# proiect.net
KiCad netlist of a schematic drawn in EAGLE
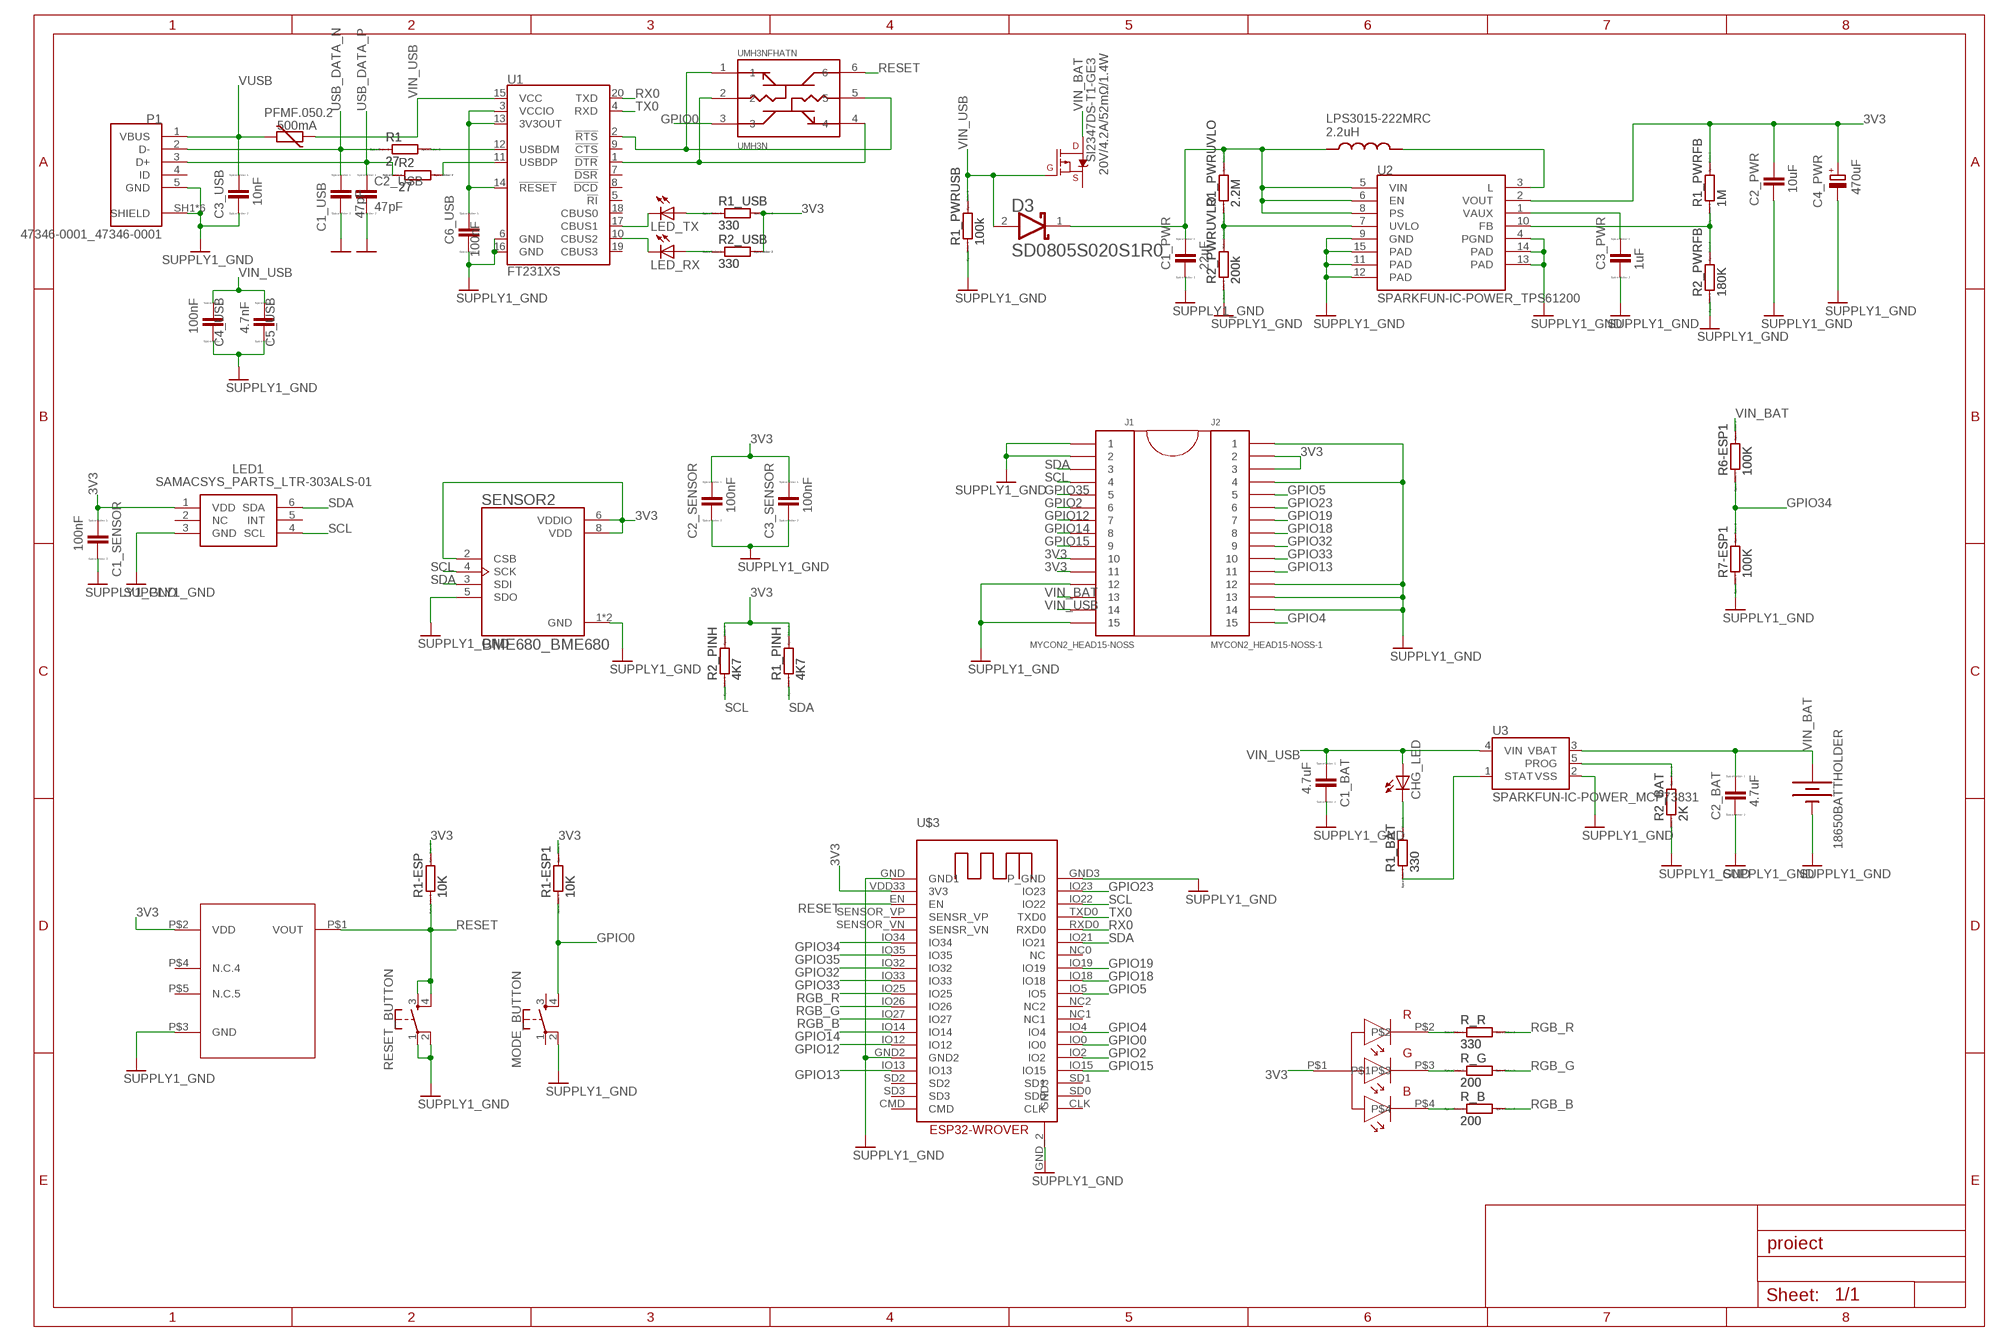
[diagram p0: schematic, sheet 1]

(export (version "E")
  (design (tool "Eeschema 10.0.6"))
  (components
    (comp (ref "18650BATTHOLDER")
      (value "BATTERY-18650")
      (footprint "eagle-import:BATTERY_18650-HOLDER")
      (libsource (lib "eagle-import") (part "BATTERY-18650"))
    )
    (comp (ref "C1_BAT")
      (value "4.7uF")
      (footprint "eagle-import:EAGLE-LTSPICE_C0402")
      (libsource (lib "eagle-import") (part "EAGLE-LTSPICE_CC0402"))
    )
    (comp (ref "C1_PWR")
      (value "22uF")
      (footprint "eagle-import:EAGLE-LTSPICE_C0402")
      (libsource (lib "eagle-import") (part "EAGLE-LTSPICE_CC0402"))
    )
    (comp (ref "C1_SENSOR")
      (value "100nF")
      (footprint "eagle-import:EAGLE-LTSPICE_C0402")
      (libsource (lib "eagle-import") (part "EAGLE-LTSPICE_CC0402"))
    )
    (comp (ref "C1_USB")
      (value "47pF")
      (footprint "eagle-import:EAGLE-LTSPICE_C0402")
      (libsource (lib "eagle-import") (part "EAGLE-LTSPICE_CC0402"))
    )
    (comp (ref "C2_BAT")
      (value "4.7uF")
      (footprint "eagle-import:EAGLE-LTSPICE_C0402")
      (libsource (lib "eagle-import") (part "EAGLE-LTSPICE_CC0402"))
    )
    (comp (ref "C2_PWR")
      (value "10uF")
      (footprint "eagle-import:RCL_C0603")
      (libsource (lib "eagle-import") (part "RCL_C-EUC0603"))
    )
    (comp (ref "C2_SENSOR")
      (value "100nF")
      (footprint "eagle-import:EAGLE-LTSPICE_C0402")
      (libsource (lib "eagle-import") (part "EAGLE-LTSPICE_CC0402"))
    )
    (comp (ref "C2_USB")
      (value "47pF")
      (footprint "eagle-import:EAGLE-LTSPICE_C0402")
      (libsource (lib "eagle-import") (part "EAGLE-LTSPICE_CC0402"))
    )
    (comp (ref "C3_PWR")
      (value "1uF")
      (footprint "eagle-import:EAGLE-LTSPICE_C0402")
      (libsource (lib "eagle-import") (part "EAGLE-LTSPICE_CC0402"))
    )
    (comp (ref "C3_SENSOR")
      (value "100nF")
      (footprint "eagle-import:EAGLE-LTSPICE_C0402")
      (libsource (lib "eagle-import") (part "EAGLE-LTSPICE_CC0402"))
    )
    (comp (ref "C3_USB")
      (value "10nF")
      (footprint "eagle-import:EAGLE-LTSPICE_C0402")
      (libsource (lib "eagle-import") (part "EAGLE-LTSPICE_CC0402"))
    )
    (comp (ref "C4_PWR")
      (value "470uF")
      (footprint "eagle-import:RCL_D_7343-31R")
      (libsource (lib "eagle-import") (part "RCL_CPOL-EUD/7343-31R"))
    )
    (comp (ref "C4_USB")
      (value "100nF")
      (footprint "eagle-import:EAGLE-LTSPICE_C0402")
      (libsource (lib "eagle-import") (part "EAGLE-LTSPICE_CC0402"))
    )
    (comp (ref "C5_USB")
      (value "4.7nF")
      (footprint "eagle-import:EAGLE-LTSPICE_C0402")
      (libsource (lib "eagle-import") (part "EAGLE-LTSPICE_CC0402"))
    )
    (comp (ref "C6_USB")
      (value "100nF")
      (footprint "eagle-import:EAGLE-LTSPICE_C0402")
      (libsource (lib "eagle-import") (part "EAGLE-LTSPICE_CC0402"))
    )
    (comp (ref "CHG_LED")
      (value "ADAFRUIT_LEDCHIP-LED0603")
      (footprint "eagle-import:ADAFRUIT_CHIP-LED0603")
      (libsource (lib "eagle-import") (part "ADAFRUIT_LEDCHIP-LED0603"))
    )
    (comp (ref "D3")
      (value "AVX---SD0805S020S1R0_AVX_SD0805S020S1R0AVX_SD0805S020S1R0_0_0")
      (footprint "eagle-import:AVX---SD0805S020S1R0_AVX_SD0805S020S1R0_0")
      (fields
        (field (name "DIGIKEY_PART_NUMBER") "478-7800-1-ND")
        (field (name "MF") "AVX")
        (field (name "MOUSER_PART_NUMBER") "581-SD0805S020S1R0")
      )
      (libsource (lib "eagle-import") (part "AVX---SD0805S020S1R0_AVX_SD0805S020S1R0AVX_SD0805S020S1R0_0_0"))
    )
    (comp (ref "J1")
      (value "MYCON2_HEAD15-NOSS")
      (footprint "eagle-import:MYCON2_HEAD15-NOSS")
      (libsource (lib "eagle-import") (part "MYCON2_HEAD15-NOSS"))
    )
    (comp (ref "J2")
      (value "MYCON2_HEAD15-NOSS-1")
      (footprint "eagle-import:MYCON2_HEAD15-NOSS-1")
      (libsource (lib "eagle-import") (part "MYCON2_HEAD15-NOSS-1"))
    )
    (comp (ref "LED1")
      (value "SAMACSYS_PARTS_LTR-303ALS-01")
      (footprint "eagle-import:SAMACSYS_PARTS_LTR303ALS01")
      (fields
        (field (name "ARROW_PART_NUMBER") "LTR-303ALS-01")
        (field (name "MOUSER_PART_NUMBER") "859-LTR-303ALS-01")
      )
      (libsource (lib "eagle-import") (part "SAMACSYS_PARTS_LTR-303ALS-01"))
    )
    (comp (ref "LED_RX")
      (value "ADAFRUIT_LEDCHIP-LED0603")
      (footprint "eagle-import:ADAFRUIT_CHIP-LED0603")
      (libsource (lib "eagle-import") (part "ADAFRUIT_LEDCHIP-LED0603"))
    )
    (comp (ref "LED_TX")
      (value "ADAFRUIT_LEDCHIP-LED0603")
      (footprint "eagle-import:ADAFRUIT_CHIP-LED0603")
      (libsource (lib "eagle-import") (part "ADAFRUIT_LEDCHIP-LED0603"))
    )
    (comp (ref "MODE_BUTTON")
      (value "SPARKFUN-SWITCHES_MOMENTARY-SWITCH-SPST-2-SMD-4.6X2.8MM")
      (footprint "eagle-import:SPARKFUN-SWITCHES_TACTILE_SWITCH_SMD_4.6X2.8MM")
      (libsource (lib "eagle-import") (part "SPARKFUN-SWITCHES_MOMENTARY-SWITCH-SPST-2-SMD-4.6X2.8MM"))
    )
    (comp (ref "P1")
      (value "47346-0001_47346-0001")
      (footprint "eagle-import:47346-0001_MOLEX_47346-0001")
      (fields (field (name "MF") "Molex") (field (name "MP") "47346-0001"))
      (libsource (lib "eagle-import") (part "47346-0001_47346-0001"))
    )
    (comp (ref "PFMF.050.2")
      (value "500mA")
      (footprint "eagle-import:VARISTOR_CT_CN1812")
      (libsource (lib "eagle-import") (part "VARISTOR_VARISTORCN1812"))
    )
    (comp (ref "R1")
      (value "27")
      (footprint "eagle-import:EAGLE-LTSPICE_R0402")
      (libsource (lib "eagle-import") (part "EAGLE-LTSPICE_R?R0402"))
    )
    (comp (ref "R1-ESP")
      (value "10K")
      (footprint "eagle-import:EAGLE-LTSPICE_R0402")
      (libsource (lib "eagle-import") (part "EAGLE-LTSPICE_R?R0402"))
    )
    (comp (ref "R1-ESP1")
      (value "10K")
      (footprint "eagle-import:EAGLE-LTSPICE_R0402")
      (libsource (lib "eagle-import") (part "EAGLE-LTSPICE_R?R0402"))
    )
    (comp (ref "R1_BAT")
      (value "330")
      (footprint "eagle-import:EAGLE-LTSPICE_R0402")
      (libsource (lib "eagle-import") (part "EAGLE-LTSPICE_R?R0402"))
    )
    (comp (ref "R1_PINH")
      (value "4K7")
      (footprint "eagle-import:EAGLE-LTSPICE_R0402")
      (libsource (lib "eagle-import") (part "EAGLE-LTSPICE_R?R0402"))
    )
    (comp (ref "R1_PWRFB")
      (value "1M")
      (footprint "eagle-import:EAGLE-LTSPICE_R0402")
      (libsource (lib "eagle-import") (part "EAGLE-LTSPICE_R?R0402"))
    )
    (comp (ref "R1_PWRUSB")
      (value "100k")
      (footprint "eagle-import:EAGLE-LTSPICE_R0402")
      (libsource (lib "eagle-import") (part "EAGLE-LTSPICE_R?R0402"))
    )
    (comp (ref "R1_PWRUVLO")
      (value "2.2M")
      (footprint "eagle-import:EAGLE-LTSPICE_R0402")
      (libsource (lib "eagle-import") (part "EAGLE-LTSPICE_R?R0402"))
    )
    (comp (ref "R1_USB")
      (value "330")
      (footprint "eagle-import:EAGLE-LTSPICE_R0402")
      (libsource (lib "eagle-import") (part "EAGLE-LTSPICE_R?R0402"))
    )
    (comp (ref "R2")
      (value "27")
      (footprint "eagle-import:EAGLE-LTSPICE_R0402")
      (libsource (lib "eagle-import") (part "EAGLE-LTSPICE_R?R0402"))
    )
    (comp (ref "R2_BAT")
      (value "2K")
      (footprint "eagle-import:EAGLE-LTSPICE_R0402")
      (libsource (lib "eagle-import") (part "EAGLE-LTSPICE_R?R0402"))
    )
    (comp (ref "R2_PINH")
      (value "4K7")
      (footprint "eagle-import:EAGLE-LTSPICE_R0402")
      (libsource (lib "eagle-import") (part "EAGLE-LTSPICE_R?R0402"))
    )
    (comp (ref "R2_PWRFB")
      (value "180K")
      (footprint "eagle-import:EAGLE-LTSPICE_R0402")
      (libsource (lib "eagle-import") (part "EAGLE-LTSPICE_R?R0402"))
    )
    (comp (ref "R2_PWRUVLO")
      (value "200k")
      (footprint "eagle-import:EAGLE-LTSPICE_R0402")
      (libsource (lib "eagle-import") (part "EAGLE-LTSPICE_R?R0402"))
    )
    (comp (ref "R2_USB")
      (value "330")
      (footprint "eagle-import:EAGLE-LTSPICE_R0402")
      (libsource (lib "eagle-import") (part "EAGLE-LTSPICE_R?R0402"))
    )
    (comp (ref "R6-ESP1")
      (value "100K")
      (footprint "eagle-import:EAGLE-LTSPICE_R0402")
      (libsource (lib "eagle-import") (part "EAGLE-LTSPICE_R?R0402"))
    )
    (comp (ref "R7-ESP1")
      (value "100K")
      (footprint "eagle-import:EAGLE-LTSPICE_R0402")
      (libsource (lib "eagle-import") (part "EAGLE-LTSPICE_R?R0402"))
    )
    (comp (ref "RESET_BUTTON")
      (value "SPARKFUN-SWITCHES_MOMENTARY-SWITCH-SPST-2-SMD-4.6X2.8MM")
      (footprint "eagle-import:SPARKFUN-SWITCHES_TACTILE_SWITCH_SMD_4.6X2.8MM")
      (libsource (lib "eagle-import") (part "SPARKFUN-SWITCHES_MOMENTARY-SWITCH-SPST-2-SMD-4.6X2.8MM"))
    )
    (comp (ref "R_B")
      (value "200")
      (footprint "eagle-import:EAGLE-LTSPICE_R0402")
      (libsource (lib "eagle-import") (part "EAGLE-LTSPICE_R?R0402"))
    )
    (comp (ref "R_G")
      (value "200")
      (footprint "eagle-import:EAGLE-LTSPICE_R0402")
      (libsource (lib "eagle-import") (part "EAGLE-LTSPICE_R?R0402"))
    )
    (comp (ref "R_R")
      (value "330")
      (footprint "eagle-import:EAGLE-LTSPICE_R0402")
      (libsource (lib "eagle-import") (part "EAGLE-LTSPICE_R?R0402"))
    )
    (comp (ref "SENSOR2")
      (value "BME680_BME680")
      (footprint "eagle-import:BME680_PSON80P300X300X100-8N")
      (fields (field (name "MF") "Bosch Sensortec") (field (name "MP") "BME680"))
      (libsource (lib "eagle-import") (part "BME680_BME680"))
    )
    (comp (ref "SI2347DS-T1-GE3")
      (value "20V/4.2A/52mΩ/1.4W")
      (footprint "eagle-import:SPARKFUN-DISCRETESEMI_SOT23-3")
      (libsource (lib "eagle-import") (part "SPARKFUN-DISCRETESEMI_MOSFET_PCH-DMG2305UX-7"))
    )
    (comp (ref "U$1")
      (value "LPS3015_LPS3015")
      (footprint "eagle-import:LPS3015_LPS3015-222MRC")
      (libsource (lib "eagle-import") (part "LPS3015_LPS3015"))
    )
    (comp (ref "U$2")
      (value "BD48E27G-TR_BD48E27G-TR")
      (footprint "eagle-import:BD48E27G-TR_SSOP5")
      (libsource (lib "eagle-import") (part "BD48E27G-TR_BD48E27G-TR"))
    )
    (comp (ref "U$3")
      (value "ESP32-WROVER_ESP32-WROVER")
      (footprint "eagle-import:ESP32-WROVER_ESP32-WROVER")
      (libsource (lib "eagle-import") (part "ESP32-WROVER_ESP32-WROVER"))
    )
    (comp (ref "U$4")
      (value "150202M153130_150202M153130-RGB")
      (footprint "eagle-import:150202M153130_150202M153130")
      (libsource (lib "eagle-import") (part "150202M153130_150202M153130-RGB"))
    )
    (comp (ref "U1")
      (value "FT231XS")
      (footprint "eagle-import:SPARKFUN-IC-COMMS_SSOP20_L")
      (libsource (lib "eagle-import") (part "SPARKFUN-IC-COMMS_FT231XS"))
    )
    (comp (ref "U2")
      (value "SPARKFUN-IC-POWER_TPS61200")
      (footprint "eagle-import:SPARKFUN-IC-POWER_QFN-10_PAD")
      (libsource (lib "eagle-import") (part "SPARKFUN-IC-POWER_TPS61200"))
    )
    (comp (ref "U3")
      (value "SPARKFUN-IC-POWER_MCP73831")
      (footprint "eagle-import:SPARKFUN-IC-POWER_SOT23-5")
      (libsource (lib "eagle-import") (part "SPARKFUN-IC-POWER_MCP73831"))
    )
    (comp (ref "UMH3NFHATN")
      (value "UMH3N_UMH3N")
      (footprint "eagle-import:UMH3N_SOP65P210X100-6N")
      (fields (field (name "MF") "Rohm") (field (name "MP") "UMH3N"))
      (libsource (lib "eagle-import") (part "UMH3N_UMH3N"))
    )
  )
  (nets
    (net (code "1") (name "/3V3") (class "Default")
      (node (ref "C1_SENSOR") (pin "1") (pinfunction "1_1") (pintype "passive"))
      (node (ref "C2_PWR") (pin "1") (pinfunction "1_1") (pintype "passive"))
      (node (ref "C2_SENSOR") (pin "1") (pinfunction "1_1") (pintype "passive"))
      (node (ref "C3_SENSOR") (pin "1") (pinfunction "1_1") (pintype "passive"))
      (node (ref "C4_PWR") (pin "+") (pinfunction "+_+") (pintype "passive"))
      (node (ref "J1") (pin "10") (pinfunction "10_10") (pintype "passive"))
      (node (ref "J1") (pin "11") (pinfunction "11_11") (pintype "passive"))
      (node (ref "J2") (pin "2") (pinfunction "2_2") (pintype "passive"))
      (node (ref "J2") (pin "3") (pinfunction "3_3") (pintype "passive"))
      (node (ref "LED1") (pin "1") (pinfunction "VDD_1") (pintype "bidirectional"))
      (node (ref "R1-ESP") (pin "2") (pinfunction "2_2") (pintype "passive"))
      (node (ref "R1-ESP1") (pin "2") (pinfunction "2_2") (pintype "passive"))
      (node (ref "R1_PINH") (pin "2") (pinfunction "2_2") (pintype "passive"))
      (node (ref "R1_PWRFB") (pin "2") (pinfunction "2_2") (pintype "passive"))
      (node (ref "R1_USB") (pin "2") (pinfunction "2_2") (pintype "passive"))
      (node (ref "R2_PINH") (pin "2") (pinfunction "2_2") (pintype "passive"))
      (node (ref "R2_USB") (pin "2") (pinfunction "2_2") (pintype "passive"))
      (node (ref "SENSOR2") (pin "2") (pinfunction "CSB_2") (pintype "input"))
      (node (ref "SENSOR2") (pin "6") (pinfunction "VDDIO_6") (pintype "power_in"))
      (node (ref "SENSOR2") (pin "8") (pinfunction "VDD_8") (pintype "power_in"))
      (node (ref "U$2") (pin "P$2") (pinfunction "VDD_P$2") (pintype "bidirectional"))
      (node (ref "U$3") (pin "VDD33") (pinfunction "3V3_VDD33") (pintype "bidirectional"))
      (node (ref "U$4") (pin "P$1") (pinfunction "P$1_P$1") (pintype "bidirectional"))
      (node (ref "U2") (pin "2") (pinfunction "VOUT_2") (pintype "passive"))
    )
    (net (code "2") (name "/GPIO0") (class "Default")
      (node (ref "MODE_BUTTON") (pin "4") (pinfunction "4_4") (pintype "passive"))
      (node (ref "R1-ESP1") (pin "1") (pinfunction "1_1") (pintype "passive"))
      (node (ref "U$3") (pin "IO0") (pinfunction "IO0_IO0") (pintype "bidirectional"))
      (node (ref "UMH3NFHATN") (pin "3") (pinfunction "3_3") (pintype "bidirectional"))
    )
    (net (code "3") (name "/GPIO2") (class "Default")
      (node (ref "J1") (pin "6") (pinfunction "6_6") (pintype "passive"))
      (node (ref "U$3") (pin "IO2") (pinfunction "IO2_IO2") (pintype "bidirectional"))
    )
    (net (code "4") (name "/GPIO4") (class "Default")
      (node (ref "J2") (pin "15") (pinfunction "15_15") (pintype "passive"))
      (node (ref "U$3") (pin "IO4") (pinfunction "IO4_IO4") (pintype "bidirectional"))
    )
    (net (code "5") (name "/GPIO5") (class "Default")
      (node (ref "J2") (pin "5") (pinfunction "5_5") (pintype "passive"))
      (node (ref "U$3") (pin "IO5") (pinfunction "IO5_IO5") (pintype "bidirectional"))
    )
    (net (code "6") (name "/GPIO12") (class "Default")
      (node (ref "J1") (pin "7") (pinfunction "7_7") (pintype "passive"))
      (node (ref "U$3") (pin "IO12") (pinfunction "IO12_IO12") (pintype "bidirectional"))
    )
    (net (code "7") (name "/GPIO13") (class "Default")
      (node (ref "J2") (pin "11") (pinfunction "11_11") (pintype "passive"))
      (node (ref "U$3") (pin "IO13") (pinfunction "IO13_IO13") (pintype "bidirectional"))
    )
    (net (code "8") (name "/GPIO14") (class "Default")
      (node (ref "J1") (pin "8") (pinfunction "8_8") (pintype "passive"))
      (node (ref "U$3") (pin "IO14") (pinfunction "IO14_IO14") (pintype "bidirectional"))
    )
    (net (code "9") (name "/GPIO15") (class "Default")
      (node (ref "J1") (pin "9") (pinfunction "9_9") (pintype "passive"))
      (node (ref "U$3") (pin "IO15") (pinfunction "IO15_IO15") (pintype "bidirectional"))
    )
    (net (code "10") (name "/GPIO18") (class "Default")
      (node (ref "J2") (pin "8") (pinfunction "8_8") (pintype "passive"))
      (node (ref "U$3") (pin "IO18") (pinfunction "IO18_IO18") (pintype "bidirectional"))
    )
    (net (code "11") (name "/GPIO19") (class "Default")
      (node (ref "J2") (pin "7") (pinfunction "7_7") (pintype "passive"))
      (node (ref "U$3") (pin "IO19") (pinfunction "IO19_IO19") (pintype "bidirectional"))
    )
    (net (code "12") (name "/GPIO23") (class "Default")
      (node (ref "J2") (pin "6") (pinfunction "6_6") (pintype "passive"))
      (node (ref "U$3") (pin "IO23") (pinfunction "IO23_IO23") (pintype "bidirectional"))
    )
    (net (code "13") (name "/GPIO32") (class "Default")
      (node (ref "J2") (pin "9") (pinfunction "9_9") (pintype "passive"))
      (node (ref "U$3") (pin "IO32") (pinfunction "IO32_IO32") (pintype "bidirectional"))
    )
    (net (code "14") (name "/GPIO33") (class "Default")
      (node (ref "J2") (pin "10") (pinfunction "10_10") (pintype "passive"))
      (node (ref "U$3") (pin "IO33") (pinfunction "IO33_IO33") (pintype "bidirectional"))
    )
    (net (code "15") (name "/GPIO34") (class "Default")
      (node (ref "R6-ESP1") (pin "1") (pinfunction "1_1") (pintype "passive"))
      (node (ref "R7-ESP1") (pin "2") (pinfunction "2_2") (pintype "passive"))
      (node (ref "U$3") (pin "IO34") (pinfunction "IO34_IO34") (pintype "bidirectional"))
    )
    (net (code "16") (name "/GPIO35") (class "Default")
      (node (ref "J1") (pin "5") (pinfunction "5_5") (pintype "passive"))
      (node (ref "U$3") (pin "IO35") (pinfunction "IO35_IO35") (pintype "bidirectional"))
    )
    (net (code "17") (name "/RESET") (class "Default")
      (node (ref "R1-ESP") (pin "1") (pinfunction "1_1") (pintype "passive"))
      (node (ref "RESET_BUTTON") (pin "3") (pinfunction "3_3") (pintype "passive"))
      (node (ref "RESET_BUTTON") (pin "4") (pinfunction "4_4") (pintype "passive"))
      (node (ref "U$2") (pin "P$1") (pinfunction "VOUT_P$1") (pintype "bidirectional"))
      (node (ref "U$3") (pin "EN") (pinfunction "EN_EN") (pintype "bidirectional"))
      (node (ref "UMH3NFHATN") (pin "6") (pinfunction "6_6") (pintype "bidirectional"))
    )
    (net (code "18") (name "/RGB_B") (class "Default")
      (node (ref "R_B") (pin "2") (pinfunction "2_2") (pintype "passive"))
      (node (ref "U$3") (pin "IO27") (pinfunction "IO27_IO27") (pintype "bidirectional"))
    )
    (net (code "19") (name "/RGB_G") (class "Default")
      (node (ref "R_G") (pin "2") (pinfunction "2_2") (pintype "passive"))
      (node (ref "U$3") (pin "IO26") (pinfunction "IO26_IO26") (pintype "bidirectional"))
    )
    (net (code "20") (name "/RGB_R") (class "Default")
      (node (ref "R_R") (pin "2") (pinfunction "2_2") (pintype "passive"))
      (node (ref "U$3") (pin "IO25") (pinfunction "IO25_IO25") (pintype "bidirectional"))
    )
    (net (code "21") (name "/RX0") (class "Default")
      (node (ref "U$3") (pin "RXD0") (pinfunction "RXD0_RXD0") (pintype "bidirectional"))
      (node (ref "U1") (pin "20") (pinfunction "TXD_20") (pintype "bidirectional"))
    )
    (net (code "22") (name "/SCL") (class "Default")
      (node (ref "J1") (pin "4") (pinfunction "4_4") (pintype "passive"))
      (node (ref "LED1") (pin "4") (pinfunction "SCL_4") (pintype "bidirectional"))
      (node (ref "R2_PINH") (pin "1") (pinfunction "1_1") (pintype "passive"))
      (node (ref "SENSOR2") (pin "4") (pinfunction "SCK_4") (pintype "input"))
      (node (ref "U$3") (pin "IO22") (pinfunction "IO22_IO22") (pintype "bidirectional"))
    )
    (net (code "23") (name "/SDA") (class "Default")
      (node (ref "J1") (pin "3") (pinfunction "3_3") (pintype "passive"))
      (node (ref "LED1") (pin "6") (pinfunction "SDA_6") (pintype "bidirectional"))
      (node (ref "R1_PINH") (pin "1") (pinfunction "1_1") (pintype "passive"))
      (node (ref "SENSOR2") (pin "3") (pinfunction "SDI_3") (pintype "bidirectional"))
      (node (ref "U$3") (pin "IO21") (pinfunction "IO21_IO21") (pintype "bidirectional"))
    )
    (net (code "24") (name "/TX0") (class "Default")
      (node (ref "U$3") (pin "TXD0") (pinfunction "TXD0_TXD0") (pintype "bidirectional"))
      (node (ref "U1") (pin "4") (pinfunction "RXD_4") (pintype "bidirectional"))
    )
    (net (code "25") (name "/USB_DATA_N") (class "Default")
      (node (ref "C1_USB") (pin "1") (pinfunction "1_1") (pintype "passive"))
      (node (ref "P1") (pin "2") (pinfunction "D-_2") (pintype "bidirectional"))
      (node (ref "R1") (pin "1") (pinfunction "1_1") (pintype "passive"))
    )
    (net (code "26") (name "/USB_DATA_P") (class "Default")
      (node (ref "C2_USB") (pin "1") (pinfunction "1_1") (pintype "passive"))
      (node (ref "P1") (pin "3") (pinfunction "D+_3") (pintype "bidirectional"))
      (node (ref "R2") (pin "1") (pinfunction "1_1") (pintype "passive"))
    )
    (net (code "27") (name "/VIN_BAT") (class "Default")
      (node (ref "18650BATTHOLDER") (pin "PWR@1") (pinfunction "+_PWR@1") (pintype "power_in"))
      (node (ref "C2_BAT") (pin "1") (pinfunction "1_1") (pintype "passive"))
      (node (ref "J1") (pin "13") (pinfunction "13_13") (pintype "passive"))
      (node (ref "R6-ESP1") (pin "2") (pinfunction "2_2") (pintype "passive"))
      (node (ref "SI2347DS-T1-GE3") (pin "3") (pinfunction "D_3") (pintype "bidirectional"))
      (node (ref "U3") (pin "3") (pinfunction "VBAT_3") (pintype "power_in"))
    )
    (net (code "28") (name "/VIN_USB") (class "Default")
      (node (ref "C1_BAT") (pin "1") (pinfunction "1_1") (pintype "passive"))
      (node (ref "C4_USB") (pin "1") (pinfunction "1_1") (pintype "passive"))
      (node (ref "C5_USB") (pin "1") (pinfunction "1_1") (pintype "passive"))
      (node (ref "CHG_LED") (pin "A") (pinfunction "A_A") (pintype "passive"))
      (node (ref "D3") (pin "2") (pinfunction "ANODE_2") (pintype "bidirectional"))
      (node (ref "J1") (pin "14") (pinfunction "14_14") (pintype "passive"))
      (node (ref "PFMF.050.2") (pin "1") (pinfunction "1_1") (pintype "passive"))
      (node (ref "R1_PWRUSB") (pin "2") (pinfunction "2_2") (pintype "passive"))
      (node (ref "SI2347DS-T1-GE3") (pin "1") (pinfunction "G_1") (pintype "bidirectional"))
      (node (ref "U1") (pin "15") (pinfunction "VCC_15") (pintype "bidirectional"))
      (node (ref "U3") (pin "4") (pinfunction "VIN_4") (pintype "power_in"))
    )
    (net (code "29") (name "/VUSB") (class "Default")
      (node (ref "C3_USB") (pin "1") (pinfunction "1_1") (pintype "passive"))
      (node (ref "P1") (pin "1") (pinfunction "VBUS_1") (pintype "power_in"))
      (node (ref "PFMF.050.2") (pin "2") (pinfunction "2_2") (pintype "passive"))
    )
    (net (code "30") (name "Net-(CHG_LED-PadC)") (class "Default")
      (node (ref "CHG_LED") (pin "C") (pinfunction "C_C") (pintype "passive"))
      (node (ref "R1_BAT") (pin "2") (pinfunction "2_2") (pintype "passive"))
    )
    (net (code "31") (name "Net-(D3-CATHODE)") (class "Default")
      (node (ref "C1_PWR") (pin "1") (pinfunction "1_1") (pintype "passive"))
      (node (ref "D3") (pin "1") (pinfunction "CATHODE_1") (pintype "bidirectional"))
      (node (ref "R1_PWRUVLO") (pin "2") (pinfunction "2_2") (pintype "passive"))
      (node (ref "U$1") (pin "P$1") (pinfunction "P$1_P$1") (pintype "bidirectional"))
      (node (ref "U2") (pin "5") (pinfunction "VIN_5") (pintype "power_in"))
      (node (ref "U2") (pin "6") (pinfunction "EN_6") (pintype "input"))
      (node (ref "U2") (pin "8") (pinfunction "PS_8") (pintype "input"))
    )
    (net (code "32") (name "Net-(LED_RX-PadA)") (class "Default")
      (node (ref "LED_RX") (pin "A") (pinfunction "A_A") (pintype "passive"))
      (node (ref "R2_USB") (pin "1") (pinfunction "1_1") (pintype "passive"))
    )
    (net (code "33") (name "Net-(LED_TX-PadA)") (class "Default")
      (node (ref "LED_TX") (pin "A") (pinfunction "A_A") (pintype "passive"))
      (node (ref "R1_USB") (pin "1") (pinfunction "1_1") (pintype "passive"))
    )
    (net (code "34") (name "Net-(R_B-Pad1)") (class "Default")
      (node (ref "R_B") (pin "1") (pinfunction "1_1") (pintype "passive"))
      (node (ref "U$4") (pin "P$4") (pinfunction "P$4_P$4") (pintype "bidirectional"))
    )
    (net (code "35") (name "Net-(R_G-Pad1)") (class "Default")
      (node (ref "R_G") (pin "1") (pinfunction "1_1") (pintype "passive"))
      (node (ref "U$4") (pin "P$3") (pinfunction "P$3_P$3") (pintype "bidirectional"))
    )
    (net (code "36") (name "Net-(R_R-Pad1)") (class "Default")
      (node (ref "R_R") (pin "1") (pinfunction "1_1") (pintype "passive"))
      (node (ref "U$4") (pin "P$2") (pinfunction "P$2_P$2") (pintype "bidirectional"))
    )
    (net (code "37") (name "Net-(U1-3V3OUT)") (class "Default")
      (node (ref "C6_USB") (pin "1") (pinfunction "1_1") (pintype "passive"))
      (node (ref "U1") (pin "13") (pinfunction "3V3OUT_13") (pintype "bidirectional"))
      (node (ref "U1") (pin "14") (pinfunction "~{RESET}_14") (pintype "bidirectional"))
      (node (ref "U1") (pin "3") (pinfunction "VCCIO_3") (pintype "bidirectional"))
    )
    (net (code "38") (name "Net-(U1-CBUS1)") (class "Default")
      (node (ref "LED_TX") (pin "C") (pinfunction "C_C") (pintype "passive"))
      (node (ref "U1") (pin "17") (pinfunction "CBUS1_17") (pintype "bidirectional"))
    )
    (net (code "39") (name "Net-(U1-CBUS2)") (class "Default")
      (node (ref "LED_RX") (pin "C") (pinfunction "C_C") (pintype "passive"))
      (node (ref "U1") (pin "10") (pinfunction "CBUS2_10") (pintype "bidirectional"))
    )
    (net (code "40") (name "Net-(U1-USBDM)") (class "Default")
      (node (ref "R1") (pin "2") (pinfunction "2_2") (pintype "passive"))
      (node (ref "U1") (pin "12") (pinfunction "USBDM_12") (pintype "bidirectional"))
    )
    (net (code "41") (name "Net-(U1-USBDP)") (class "Default")
      (node (ref "R2") (pin "2") (pinfunction "2_2") (pintype "passive"))
      (node (ref "U1") (pin "11") (pinfunction "USBDP_11") (pintype "bidirectional"))
    )
    (net (code "42") (name "Net-(U1-~{DTR})") (class "Default")
      (node (ref "U1") (pin "1") (pinfunction "~{DTR}_1") (pintype "bidirectional"))
      (node (ref "UMH3NFHATN") (pin "2") (pinfunction "2_2") (pintype "bidirectional"))
      (node (ref "UMH3NFHATN") (pin "4") (pinfunction "4_4") (pintype "bidirectional"))
    )
    (net (code "43") (name "Net-(U1-~{RTS})") (class "Default")
      (node (ref "U1") (pin "2") (pinfunction "~{RTS}_2") (pintype "bidirectional"))
      (node (ref "UMH3NFHATN") (pin "1") (pinfunction "1_1") (pintype "bidirectional"))
      (node (ref "UMH3NFHATN") (pin "5") (pinfunction "5_5") (pintype "bidirectional"))
    )
    (net (code "44") (name "Net-(U2-FB)") (class "Default")
      (node (ref "R1_PWRFB") (pin "1") (pinfunction "1_1") (pintype "passive"))
      (node (ref "R2_PWRFB") (pin "2") (pinfunction "2_2") (pintype "passive"))
      (node (ref "U2") (pin "10") (pinfunction "FB_10") (pintype "passive"))
    )
    (net (code "45") (name "Net-(U2-L)") (class "Default")
      (node (ref "U$1") (pin "P$2") (pinfunction "P$2_P$2") (pintype "bidirectional"))
      (node (ref "U2") (pin "3") (pinfunction "L_3") (pintype "passive"))
    )
    (net (code "46") (name "Net-(U2-UVLO)") (class "Default")
      (node (ref "R1_PWRUVLO") (pin "1") (pinfunction "1_1") (pintype "passive"))
      (node (ref "R2_PWRUVLO") (pin "2") (pinfunction "2_2") (pintype "passive"))
      (node (ref "U2") (pin "7") (pinfunction "UVLO_7") (pintype "passive"))
    )
    (net (code "47") (name "Net-(U2-VAUX)") (class "Default")
      (node (ref "C3_PWR") (pin "1") (pinfunction "1_1") (pintype "passive"))
      (node (ref "U2") (pin "1") (pinfunction "VAUX_1") (pintype "passive"))
    )
    (net (code "48") (name "Net-(U3-PROG)") (class "Default")
      (node (ref "R2_BAT") (pin "2") (pinfunction "2_2") (pintype "passive"))
      (node (ref "U3") (pin "5") (pinfunction "PROG_5") (pintype "input"))
    )
    (net (code "49") (name "Net-(U3-STAT)") (class "Default")
      (node (ref "R1_BAT") (pin "1") (pinfunction "1_1") (pintype "passive"))
      (node (ref "U3") (pin "1") (pinfunction "STAT_1") (pintype "output"))
    )
    (net (code "50") (name "SUPPLY1_GND") (class "Default")
      (node (ref "18650BATTHOLDER") (pin "GND@1") (pinfunction "-_GND@1") (pintype "power_in"))
      (node (ref "C1_BAT") (pin "2") (pinfunction "2_2") (pintype "passive"))
      (node (ref "C1_PWR") (pin "2") (pinfunction "2_2") (pintype "passive"))
      (node (ref "C1_SENSOR") (pin "2") (pinfunction "2_2") (pintype "passive"))
      (node (ref "C1_USB") (pin "2") (pinfunction "2_2") (pintype "passive"))
      (node (ref "C2_BAT") (pin "2") (pinfunction "2_2") (pintype "passive"))
      (node (ref "C2_PWR") (pin "2") (pinfunction "2_2") (pintype "passive"))
      (node (ref "C2_SENSOR") (pin "2") (pinfunction "2_2") (pintype "passive"))
      (node (ref "C2_USB") (pin "2") (pinfunction "2_2") (pintype "passive"))
      (node (ref "C3_PWR") (pin "2") (pinfunction "2_2") (pintype "passive"))
      (node (ref "C3_SENSOR") (pin "2") (pinfunction "2_2") (pintype "passive"))
      (node (ref "C3_USB") (pin "2") (pinfunction "2_2") (pintype "passive"))
      (node (ref "C4_PWR") (pin "-") (pinfunction "-_-") (pintype "passive"))
      (node (ref "C4_USB") (pin "2") (pinfunction "2_2") (pintype "passive"))
      (node (ref "C5_USB") (pin "2") (pinfunction "2_2") (pintype "passive"))
      (node (ref "C6_USB") (pin "2") (pinfunction "2_2") (pintype "passive"))
      (node (ref "J1") (pin "1") (pinfunction "1_1") (pintype "passive"))
      (node (ref "J1") (pin "12") (pinfunction "12_12") (pintype "passive"))
      (node (ref "J1") (pin "15") (pinfunction "15_15") (pintype "passive"))
      (node (ref "J1") (pin "2") (pinfunction "2_2") (pintype "passive"))
      (node (ref "J2") (pin "1") (pinfunction "1_1") (pintype "passive"))
      (node (ref "J2") (pin "12") (pinfunction "12_12") (pintype "passive"))
      (node (ref "J2") (pin "13") (pinfunction "13_13") (pintype "passive"))
      (node (ref "J2") (pin "14") (pinfunction "14_14") (pintype "passive"))
      (node (ref "J2") (pin "4") (pinfunction "4_4") (pintype "passive"))
      (node (ref "LED1") (pin "3") (pinfunction "GND_3") (pintype "bidirectional"))
      (node (ref "MODE_BUTTON") (pin "2") (pinfunction "2_2") (pintype "passive"))
      (node (ref "P1") (pin "5") (pinfunction "GND_5") (pintype "power_in"))
      (node (ref "P1") (pin "SH1") (pinfunction "SHIELD_SH1") (pintype "passive"))
      (node (ref "P1") (pin "SH2") (pinfunction "SHIELD_SH2") (pintype "passive"))
      (node (ref "P1") (pin "SH3") (pinfunction "SHIELD_SH3") (pintype "passive"))
      (node (ref "P1") (pin "SH4") (pinfunction "SHIELD_SH4") (pintype "passive"))
      (node (ref "P1") (pin "SH5") (pinfunction "SHIELD_SH5") (pintype "passive"))
      (node (ref "P1") (pin "SH6") (pinfunction "SHIELD_SH6") (pintype "passive"))
      (node (ref "R1_PWRUSB") (pin "1") (pinfunction "1_1") (pintype "passive"))
      (node (ref "R2_BAT") (pin "1") (pinfunction "1_1") (pintype "passive"))
      (node (ref "R2_PWRFB") (pin "1") (pinfunction "1_1") (pintype "passive"))
      (node (ref "R2_PWRUVLO") (pin "1") (pinfunction "1_1") (pintype "passive"))
      (node (ref "R7-ESP1") (pin "1") (pinfunction "1_1") (pintype "passive"))
      (node (ref "RESET_BUTTON") (pin "1") (pinfunction "1_1") (pintype "passive"))
      (node (ref "RESET_BUTTON") (pin "2") (pinfunction "2_2") (pintype "passive"))
      (node (ref "SENSOR2") (pin "1") (pinfunction "GND_1") (pintype "power_in"))
      (node (ref "SENSOR2") (pin "5") (pinfunction "SDO_5") (pintype "bidirectional"))
      (node (ref "SENSOR2") (pin "7") (pinfunction "GND_7") (pintype "power_in"))
      (node (ref "U$2") (pin "P$3") (pinfunction "GND_P$3") (pintype "bidirectional"))
      (node (ref "U$3") (pin "GND") (pinfunction "GND1_GND") (pintype "bidirectional"))
      (node (ref "U$3") (pin "GND2") (pinfunction "GND2_GND2") (pintype "bidirectional"))
      (node (ref "U$3") (pin "GND3") (pinfunction "P_GND_GND3") (pintype "bidirectional"))
      (node (ref "U$3") (pin "GND_2") (pinfunction "GND3_GND_2") (pintype "bidirectional"))
      (node (ref "U1") (pin "16") (pinfunction "GND_16") (pintype "bidirectional"))
      (node (ref "U1") (pin "6") (pinfunction "GND_6") (pintype "bidirectional"))
      (node (ref "U2") (pin "11") (pinfunction "PAD_11") (pintype "power_in"))
      (node (ref "U2") (pin "12") (pinfunction "PAD_12") (pintype "power_in"))
      (node (ref "U2") (pin "13") (pinfunction "PAD_13") (pintype "power_in"))
      (node (ref "U2") (pin "14") (pinfunction "PAD_14") (pintype "power_in"))
      (node (ref "U2") (pin "15") (pinfunction "PAD_15") (pintype "power_in"))
      (node (ref "U2") (pin "4") (pinfunction "PGND_4") (pintype "power_in"))
      (node (ref "U2") (pin "9") (pinfunction "GND_9") (pintype "power_in"))
      (node (ref "U3") (pin "2") (pinfunction "VSS_2") (pintype "power_in"))
    )
    (net (code "51") (name "unconnected-(LED1-INT-Pad5)") (class "Default")
      (node (ref "LED1") (pin "5") (pinfunction "INT_5") (pintype "bidirectional"))
    )
    (net (code "52") (name "unconnected-(LED1-NC-Pad2)") (class "Default")
      (node (ref "LED1") (pin "2") (pinfunction "NC_2") (pintype "no_connect"))
    )
    (net (code "53") (name "unconnected-(MODE_BUTTON-Pad1)") (class "Default")
      (node (ref "MODE_BUTTON") (pin "1") (pinfunction "1_1") (pintype "passive"))
    )
    (net (code "54") (name "unconnected-(MODE_BUTTON-Pad3)") (class "Default")
      (node (ref "MODE_BUTTON") (pin "3") (pinfunction "3_3") (pintype "passive"))
    )
    (net (code "55") (name "unconnected-(P1-ID-Pad4)") (class "Default")
      (node (ref "P1") (pin "4") (pinfunction "ID_4") (pintype "passive"))
    )
    (net (code "56") (name "unconnected-(SI2347DS-T1-GE3-S-Pad2)") (class "Default")
      (node (ref "SI2347DS-T1-GE3") (pin "2") (pinfunction "S_2") (pintype "bidirectional"))
    )
    (net (code "57") (name "unconnected-(U$2-N.C.4-PadP$4)") (class "Default")
      (node (ref "U$2") (pin "P$4") (pinfunction "N.C.4_P$4") (pintype "bidirectional"))
    )
    (net (code "58") (name "unconnected-(U$2-N.C.5-PadP$5)") (class "Default")
      (node (ref "U$2") (pin "P$5") (pinfunction "N.C.5_P$5") (pintype "bidirectional"))
    )
    (net (code "59") (name "unconnected-(U$3-NC-PadNC0)") (class "Default")
      (node (ref "U$3") (pin "NC0") (pinfunction "NC_NC0") (pintype "bidirectional"))
    )
    (net (code "60") (name "unconnected-(U$3-PadCLK)") (class "Default")
      (node (ref "U$3") (pin "CLK") (pinfunction "CLK_CLK") (pintype "bidirectional"))
    )
    (net (code "61") (name "unconnected-(U$3-PadCMD)") (class "Default")
      (node (ref "U$3") (pin "CMD") (pinfunction "CMD_CMD") (pintype "bidirectional"))
    )
    (net (code "62") (name "unconnected-(U$3-PadNC1)") (class "Default")
      (node (ref "U$3") (pin "NC1") (pinfunction "NC1_NC1") (pintype "bidirectional"))
    )
    (net (code "63") (name "unconnected-(U$3-PadNC2)") (class "Default")
      (node (ref "U$3") (pin "NC2") (pinfunction "NC2_NC2") (pintype "bidirectional"))
    )
    (net (code "64") (name "unconnected-(U$3-PadSD0)") (class "Default")
      (node (ref "U$3") (pin "SD0") (pinfunction "SD0_SD0") (pintype "bidirectional"))
    )
    (net (code "65") (name "unconnected-(U$3-PadSD1)") (class "Default")
      (node (ref "U$3") (pin "SD1") (pinfunction "SD1_SD1") (pintype "bidirectional"))
    )
    (net (code "66") (name "unconnected-(U$3-PadSD2)") (class "Default")
      (node (ref "U$3") (pin "SD2") (pinfunction "SD2_SD2") (pintype "bidirectional"))
    )
    (net (code "67") (name "unconnected-(U$3-PadSD3)") (class "Default")
      (node (ref "U$3") (pin "SD3") (pinfunction "SD3_SD3") (pintype "bidirectional"))
    )
    (net (code "68") (name "unconnected-(U$3-SENSR_VN-PadSENSOR_VN)") (class "Default")
      (node (ref "U$3") (pin "SENSOR_VN") (pinfunction "SENSR_VN_SENSOR_VN") (pintype "bidirectional"))
    )
    (net (code "69") (name "unconnected-(U$3-SENSR_VP-PadSENSOR_VP)") (class "Default")
      (node (ref "U$3") (pin "SENSOR_VP") (pinfunction "SENSR_VP_SENSOR_VP") (pintype "bidirectional"))
    )
    (net (code "70") (name "unconnected-(U1-CBUS0-Pad18)") (class "Default")
      (node (ref "U1") (pin "18") (pinfunction "CBUS0_18") (pintype "bidirectional"))
    )
    (net (code "71") (name "unconnected-(U1-CBUS3-Pad19)") (class "Default")
      (node (ref "U1") (pin "19") (pinfunction "CBUS3_19") (pintype "bidirectional"))
    )
    (net (code "72") (name "unconnected-(U1-~{CTS}-Pad9)") (class "Default")
      (node (ref "U1") (pin "9") (pinfunction "~{CTS}_9") (pintype "bidirectional"))
    )
    (net (code "73") (name "unconnected-(U1-~{DCD}-Pad8)") (class "Default")
      (node (ref "U1") (pin "8") (pinfunction "~{DCD}_8") (pintype "bidirectional"))
    )
    (net (code "74") (name "unconnected-(U1-~{DSR}-Pad7)") (class "Default")
      (node (ref "U1") (pin "7") (pinfunction "~{DSR}_7") (pintype "bidirectional"))
    )
    (net (code "75") (name "unconnected-(U1-~{RI}-Pad5)") (class "Default")
      (node (ref "U1") (pin "5") (pinfunction "~{RI}_5") (pintype "bidirectional"))
    )
  )
)
